# alarm_controller_f103.net
KiCad netlist of a schematic drawn in EAGLE
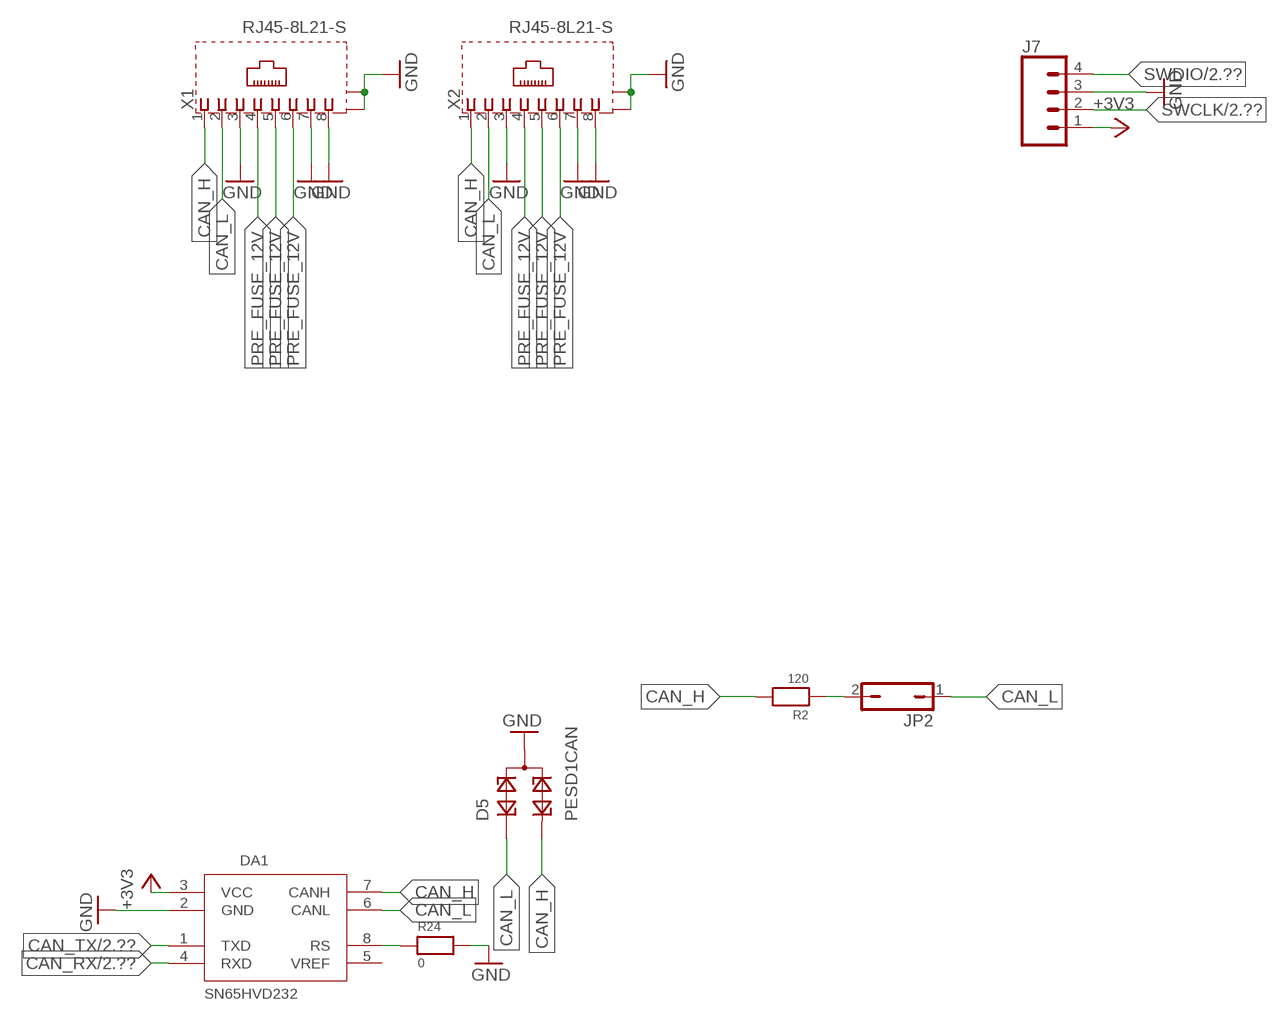
[diagram p0: schematic, sheet 1, part 1 of 2]
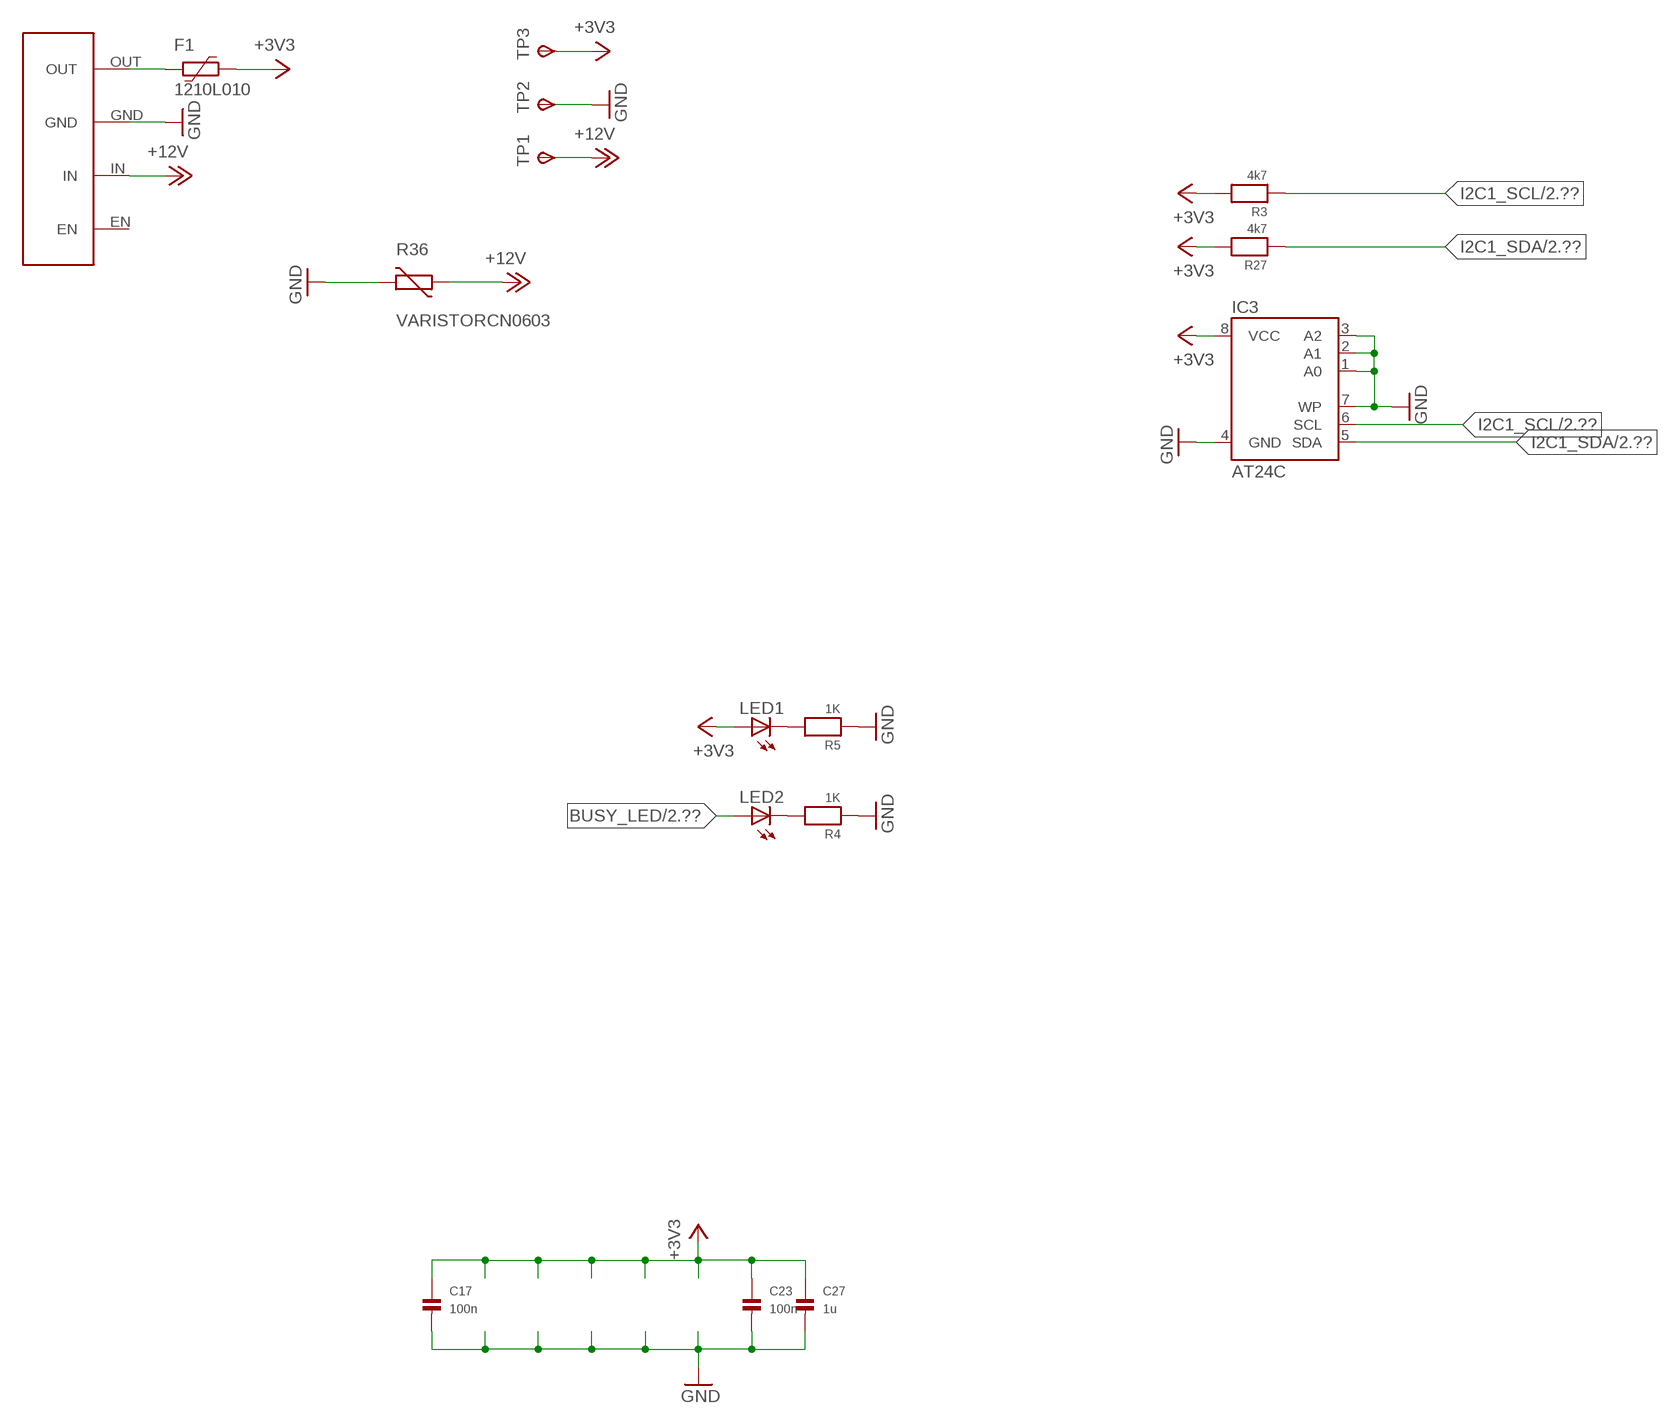
[diagram p1: schematic, sheet 1, part 2 of 2]
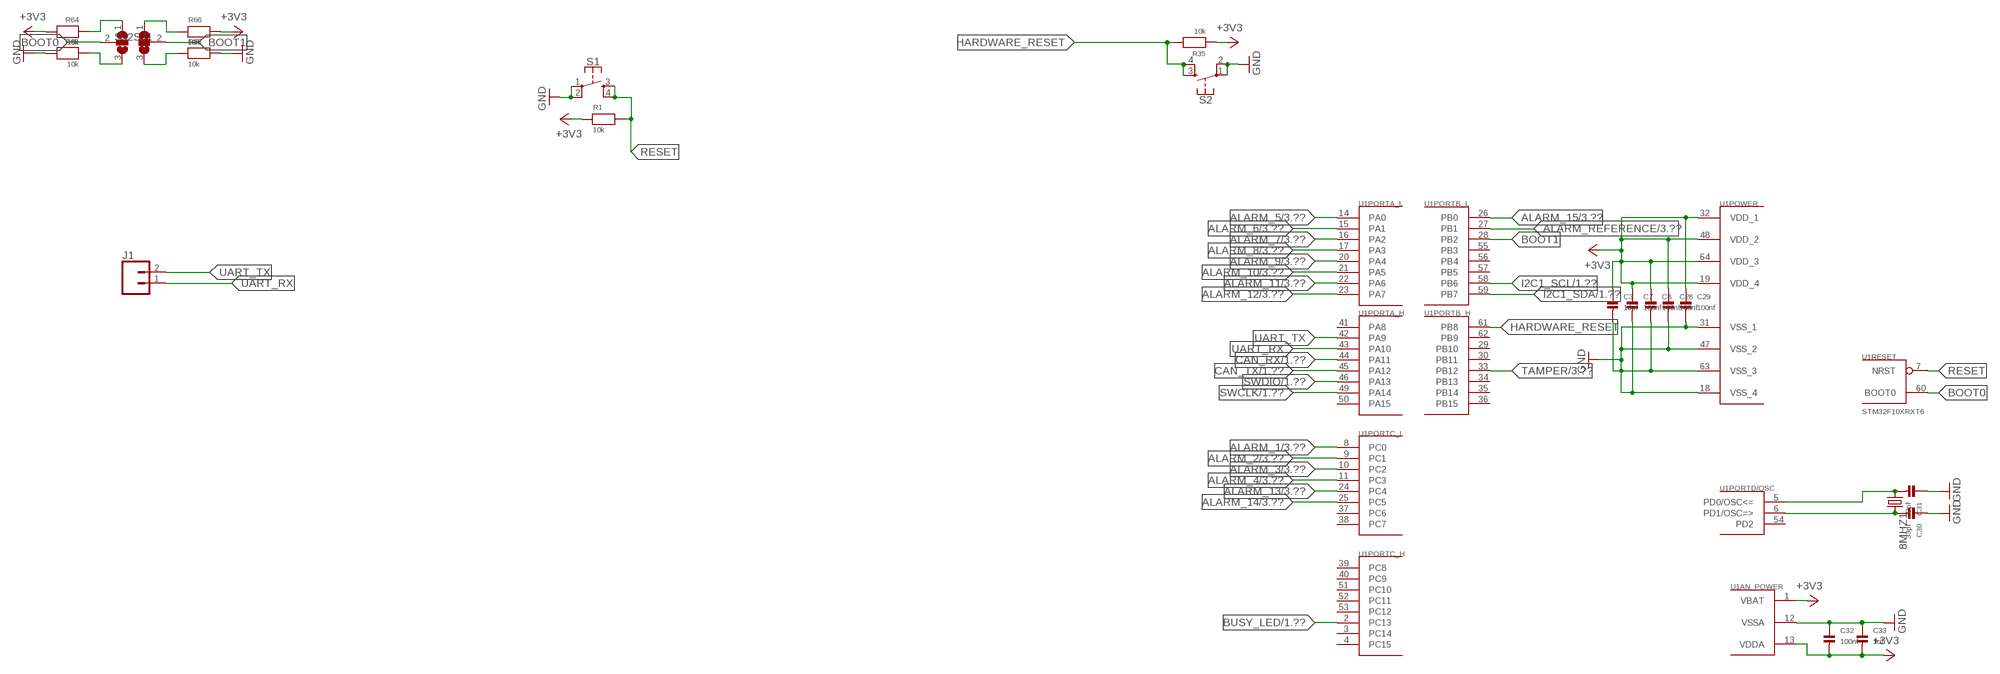
[diagram p2: schematic, sheet 2]
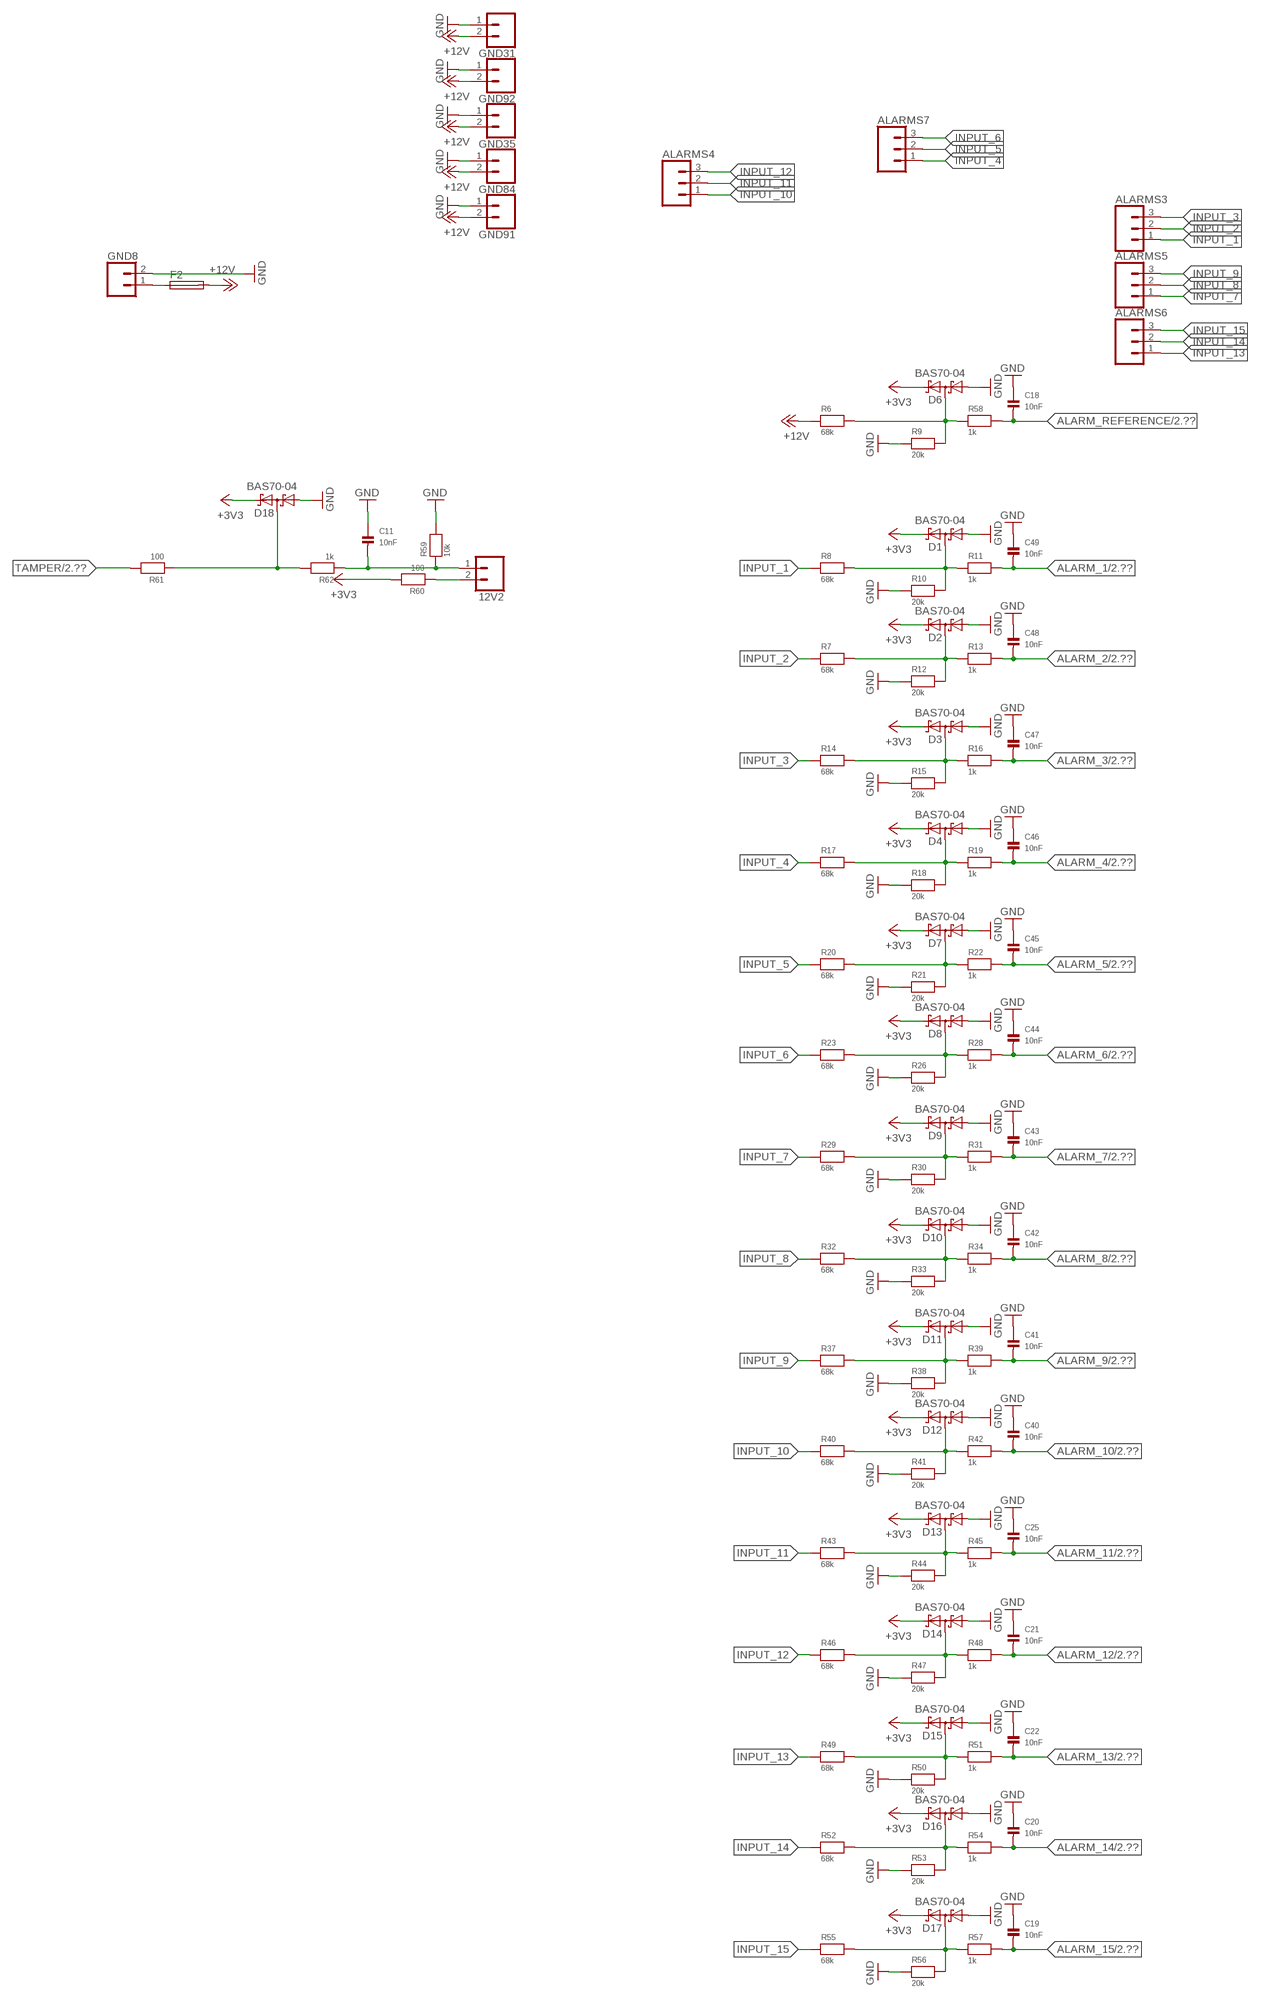
[diagram p3: schematic, sheet 3]

(export (version "E")
  (design (tool "Eeschema 10.0.6"))
  (components
    (comp (ref "C17")
      (value "100n")
      (footprint "eagle-import:0603")
      (libsource (lib "eagle-import") (part "CAP_CERAMIC0603"))
    )
    (comp (ref "C23")
      (value "100n")
      (footprint "eagle-import:0603")
      (libsource (lib "eagle-import") (part "CAP_CERAMIC0603"))
    )
    (comp (ref "C27")
      (value "1u")
      (footprint "eagle-import:0603")
      (libsource (lib "eagle-import") (part "CAP_CERAMIC0603"))
    )
    (comp (ref "D5")
      (value "PESD1CAN")
      (footprint "eagle-import:SOT23")
      (libsource (lib "eagle-import") (part "PESD1CAN"))
    )
    (comp (ref "DA1")
      (value "SN65HVD232")
      (footprint "eagle-import:SO08")
      (libsource (lib "eagle-import") (part "SN65HVD232"))
    )
    (comp (ref "F1")
      (value "1210L010")
      (footprint "eagle-import:1210L")
      (fields (field (name "MF") "Littelfuse"))
      (libsource (lib "eagle-import") (part "?1210L010"))
    )
    (comp (ref "IC3")
      (value "AT24C")
      (footprint "eagle-import:SOIC8")
      (libsource (lib "eagle-import") (part "AT24C"))
    )
    (comp (ref "J7")
      (value "CONN_04POLAR_LOCK")
      (footprint "eagle-import:MOLEX-1X4_LOCK")
      (libsource (lib "eagle-import") (part "CONN_04POLAR_LOCK"))
    )
    (comp (ref "JP2")
      (value "JP1Q")
      (footprint "eagle-import:JP1")
      (libsource (lib "eagle-import") (part "JP1Q"))
    )
    (comp (ref "LED1")
      (value "LEDCHIPLED_0805")
      (footprint "eagle-import:CHIPLED_0805")
      (libsource (lib "eagle-import") (part "LEDCHIPLED_0805"))
    )
    (comp (ref "LED2")
      (value "LEDCHIPLED_0805")
      (footprint "eagle-import:CHIPLED_0805")
      (libsource (lib "eagle-import") (part "LEDCHIPLED_0805"))
    )
    (comp (ref "R2")
      (value "120")
      (footprint "eagle-import:0603")
      (libsource (lib "eagle-import") (part "RESISTOR0603"))
    )
    (comp (ref "R3")
      (value "4k7")
      (footprint "eagle-import:0603")
      (libsource (lib "eagle-import") (part "RESISTOR0603"))
    )
    (comp (ref "R4")
      (value "1K")
      (footprint "eagle-import:0603")
      (libsource (lib "eagle-import") (part "RESISTOR0603"))
    )
    (comp (ref "R5")
      (value "1K")
      (footprint "eagle-import:0603")
      (libsource (lib "eagle-import") (part "RESISTOR0603"))
    )
    (comp (ref "R24")
      (value "0")
      (footprint "eagle-import:0603")
      (libsource (lib "eagle-import") (part "RESISTOR0603"))
    )
    (comp (ref "R27")
      (value "4k7")
      (footprint "eagle-import:0603")
      (libsource (lib "eagle-import") (part "RESISTOR0603"))
    )
    (comp (ref "R36")
      (value "VARISTORCN0603")
      (footprint "eagle-import:CT_CN0603")
      (libsource (lib "eagle-import") (part "VARISTORCN0603"))
    )
    (comp (ref "TP1")
      (value "TPSTP20R")
      (footprint "eagle-import:TP20R")
      (libsource (lib "eagle-import") (part "TPSTP20R"))
    )
    (comp (ref "TP2")
      (value "TPSTP20R")
      (footprint "eagle-import:TP20R")
      (libsource (lib "eagle-import") (part "TPSTP20R"))
    )
    (comp (ref "TP3")
      (value "TPSTP20R")
      (footprint "eagle-import:TP20R")
      (libsource (lib "eagle-import") (part "TPSTP20R"))
    )
    (comp (ref "U$4")
      (value "HW-613")
      (footprint "eagle-import:HW-613")
      (libsource (lib "eagle-import") (part "HW-613"))
    )
    (comp (ref "X1")
      (value "RJ45-8L21-S")
      (footprint "eagle-import:RJ45-SHIELD1")
      (libsource (lib "eagle-import") (part "RJ4521-S-8L"))
    )
    (comp (ref "X2")
      (value "RJ45-8L21-S")
      (footprint "eagle-import:RJ45-SHIELD1")
      (libsource (lib "eagle-import") (part "RJ4521-S-8L"))
    )
    (comp (ref "8MHZ1")
      (value "CRYSTALHC49UP")
      (footprint "eagle-import:HC49UP")
      (libsource (lib "eagle-import") (part "CRYSTALHC49UP"))
    )
    (comp (ref "C3")
      (value "10uf")
      (footprint "eagle-import:0805")
      (libsource (lib "eagle-import") (part "CAP_CERAMIC0805"))
    )
    (comp (ref "C7")
      (value "100nf")
      (footprint "eagle-import:0603-MINI")
      (libsource (lib "eagle-import") (part "CAP_CERAMIC0603MINI"))
    )
    (comp (ref "C8")
      (value "100nf")
      (footprint "eagle-import:0603-MINI")
      (libsource (lib "eagle-import") (part "CAP_CERAMIC0603MINI"))
    )
    (comp (ref "C28")
      (value "100nf")
      (footprint "eagle-import:0603-MINI")
      (libsource (lib "eagle-import") (part "CAP_CERAMIC0603MINI"))
    )
    (comp (ref "C29")
      (value "100nf")
      (footprint "eagle-import:0603-MINI")
      (libsource (lib "eagle-import") (part "CAP_CERAMIC0603MINI"))
    )
    (comp (ref "C30")
      (value "33pf")
      (footprint "eagle-import:0603")
      (libsource (lib "eagle-import") (part "CAP_CERAMIC0603"))
    )
    (comp (ref "C31")
      (value "33pf")
      (footprint "eagle-import:0603")
      (libsource (lib "eagle-import") (part "CAP_CERAMIC0603"))
    )
    (comp (ref "C32")
      (value "100nf")
      (footprint "eagle-import:0603-MINI")
      (libsource (lib "eagle-import") (part "CAP_CERAMIC0603MINI"))
    )
    (comp (ref "C33")
      (value "1uf")
      (footprint "eagle-import:0603-MINI")
      (libsource (lib "eagle-import") (part "CAP_CERAMIC0603MINI"))
    )
    (comp (ref "J1")
      (value "CONN_02")
      (footprint "eagle-import:1X02")
      (libsource (lib "eagle-import") (part "CONN_02"))
    )
    (comp (ref "R1")
      (value "10k")
      (footprint "eagle-import:0603")
      (libsource (lib "eagle-import") (part "RESISTOR0603"))
    )
    (comp (ref "R35")
      (value "10k")
      (footprint "eagle-import:0603")
      (libsource (lib "eagle-import") (part "RESISTOR0603"))
    )
    (comp (ref "R63")
      (value "10k")
      (footprint "eagle-import:0603")
      (libsource (lib "eagle-import") (part "RESISTOR0603"))
    )
    (comp (ref "R64")
      (value "10k")
      (footprint "eagle-import:0603")
      (libsource (lib "eagle-import") (part "RESISTOR0603"))
    )
    (comp (ref "R65")
      (value "10k")
      (footprint "eagle-import:0603")
      (libsource (lib "eagle-import") (part "RESISTOR0603"))
    )
    (comp (ref "R66")
      (value "10k")
      (footprint "eagle-import:0603")
      (libsource (lib "eagle-import") (part "RESISTOR0603"))
    )
    (comp (ref "S1")
      (value "MOMENTARY-SWITCH-SPST-2-SMD-4.6X2.8MM")
      (footprint "eagle-import:TACTILE_SWITCH_SMD_4.6X2.8MM")
      (libsource (lib "eagle-import") (part "MOMENTARY-SWITCH-SPST-2-SMD-4.6X2.8MM"))
    )
    (comp (ref "S2")
      (value "MOMENTARY-SWITCH-SPST-2-SMD-4.6X2.8MM")
      (footprint "eagle-import:TACTILE_SWITCH_SMD_4.6X2.8MM")
      (libsource (lib "eagle-import") (part "MOMENTARY-SWITCH-SPST-2-SMD-4.6X2.8MM"))
    )
    (comp (ref "SJ1")
      (value "SJ2W")
      (footprint "eagle-import:SJ_2")
      (libsource (lib "eagle-import") (part "SJ2W"))
    )
    (comp (ref "SJ2")
      (value "SJ2W")
      (footprint "eagle-import:SJ_2")
      (libsource (lib "eagle-import") (part "SJ2W"))
    )
    (comp (ref "U1")
      (value "STM32F10XRXT6")
      (footprint "eagle-import:TQFP64")
      (libsource (lib "eagle-import") (part "STM32F10XRXT6"))
    )
    (comp (ref "12V2")
      (value "CONN_023.5MM")
      (footprint "eagle-import:SCREWTERMINAL-3.5MM-2")
      (libsource (lib "eagle-import") (part "CONN_023.5MM"))
    )
    (comp (ref "ALARMS3")
      (value "CONN_03SCREW_LOCK")
      (footprint "eagle-import:SCREWTERMINAL-3.5MM-3_LOCK.007S")
      (libsource (lib "eagle-import") (part "CONN_03SCREW_LOCK"))
    )
    (comp (ref "ALARMS4")
      (value "CONN_03SCREW_LOCK")
      (footprint "eagle-import:SCREWTERMINAL-3.5MM-3_LOCK.007S")
      (libsource (lib "eagle-import") (part "CONN_03SCREW_LOCK"))
    )
    (comp (ref "ALARMS5")
      (value "CONN_03SCREW_LOCK")
      (footprint "eagle-import:SCREWTERMINAL-3.5MM-3_LOCK.007S")
      (libsource (lib "eagle-import") (part "CONN_03SCREW_LOCK"))
    )
    (comp (ref "ALARMS6")
      (value "CONN_03SCREW_LOCK")
      (footprint "eagle-import:SCREWTERMINAL-3.5MM-3_LOCK.007S")
      (libsource (lib "eagle-import") (part "CONN_03SCREW_LOCK"))
    )
    (comp (ref "ALARMS7")
      (value "CONN_03SCREW_LOCK")
      (footprint "eagle-import:SCREWTERMINAL-3.5MM-3_LOCK.007S")
      (libsource (lib "eagle-import") (part "CONN_03SCREW_LOCK"))
    )
    (comp (ref "C11")
      (value "10nF")
      (footprint "eagle-import:0603")
      (libsource (lib "eagle-import") (part "CAP_CERAMIC0603"))
    )
    (comp (ref "C18")
      (value "10nF")
      (footprint "eagle-import:0603")
      (libsource (lib "eagle-import") (part "CAP_CERAMIC0603"))
    )
    (comp (ref "C19")
      (value "10nF")
      (footprint "eagle-import:0603")
      (libsource (lib "eagle-import") (part "CAP_CERAMIC0603"))
    )
    (comp (ref "C20")
      (value "10nF")
      (footprint "eagle-import:0603")
      (libsource (lib "eagle-import") (part "CAP_CERAMIC0603"))
    )
    (comp (ref "C21")
      (value "10nF")
      (footprint "eagle-import:0603")
      (libsource (lib "eagle-import") (part "CAP_CERAMIC0603"))
    )
    (comp (ref "C22")
      (value "10nF")
      (footprint "eagle-import:0603")
      (libsource (lib "eagle-import") (part "CAP_CERAMIC0603"))
    )
    (comp (ref "C25")
      (value "10nF")
      (footprint "eagle-import:0603")
      (libsource (lib "eagle-import") (part "CAP_CERAMIC0603"))
    )
    (comp (ref "C40")
      (value "10nF")
      (footprint "eagle-import:0603")
      (libsource (lib "eagle-import") (part "CAP_CERAMIC0603"))
    )
    (comp (ref "C41")
      (value "10nF")
      (footprint "eagle-import:0603")
      (libsource (lib "eagle-import") (part "CAP_CERAMIC0603"))
    )
    (comp (ref "C42")
      (value "10nF")
      (footprint "eagle-import:0603")
      (libsource (lib "eagle-import") (part "CAP_CERAMIC0603"))
    )
    (comp (ref "C43")
      (value "10nF")
      (footprint "eagle-import:0603")
      (libsource (lib "eagle-import") (part "CAP_CERAMIC0603"))
    )
    (comp (ref "C44")
      (value "10nF")
      (footprint "eagle-import:0603")
      (libsource (lib "eagle-import") (part "CAP_CERAMIC0603"))
    )
    (comp (ref "C45")
      (value "10nF")
      (footprint "eagle-import:0603")
      (libsource (lib "eagle-import") (part "CAP_CERAMIC0603"))
    )
    (comp (ref "C46")
      (value "10nF")
      (footprint "eagle-import:0603")
      (libsource (lib "eagle-import") (part "CAP_CERAMIC0603"))
    )
    (comp (ref "C47")
      (value "10nF")
      (footprint "eagle-import:0603")
      (libsource (lib "eagle-import") (part "CAP_CERAMIC0603"))
    )
    (comp (ref "C48")
      (value "10nF")
      (footprint "eagle-import:0603")
      (libsource (lib "eagle-import") (part "CAP_CERAMIC0603"))
    )
    (comp (ref "C49")
      (value "10nF")
      (footprint "eagle-import:0603")
      (libsource (lib "eagle-import") (part "CAP_CERAMIC0603"))
    )
    (comp (ref "D1")
      (value "BAS70-04")
      (footprint "eagle-import:SOT23")
      (libsource (lib "eagle-import") (part "BAS70-04"))
    )
    (comp (ref "D2")
      (value "BAS70-04")
      (footprint "eagle-import:SOT23")
      (libsource (lib "eagle-import") (part "BAS70-04"))
    )
    (comp (ref "D3")
      (value "BAS70-04")
      (footprint "eagle-import:SOT23")
      (libsource (lib "eagle-import") (part "BAS70-04"))
    )
    (comp (ref "D4")
      (value "BAS70-04")
      (footprint "eagle-import:SOT23")
      (libsource (lib "eagle-import") (part "BAS70-04"))
    )
    (comp (ref "D6")
      (value "BAS70-04")
      (footprint "eagle-import:SOT23")
      (libsource (lib "eagle-import") (part "BAS70-04"))
    )
    (comp (ref "D7")
      (value "BAS70-04")
      (footprint "eagle-import:SOT23")
      (libsource (lib "eagle-import") (part "BAS70-04"))
    )
    (comp (ref "D8")
      (value "BAS70-04")
      (footprint "eagle-import:SOT23")
      (libsource (lib "eagle-import") (part "BAS70-04"))
    )
    (comp (ref "D9")
      (value "BAS70-04")
      (footprint "eagle-import:SOT23")
      (libsource (lib "eagle-import") (part "BAS70-04"))
    )
    (comp (ref "D10")
      (value "BAS70-04")
      (footprint "eagle-import:SOT23")
      (libsource (lib "eagle-import") (part "BAS70-04"))
    )
    (comp (ref "D11")
      (value "BAS70-04")
      (footprint "eagle-import:SOT23")
      (libsource (lib "eagle-import") (part "BAS70-04"))
    )
    (comp (ref "D12")
      (value "BAS70-04")
      (footprint "eagle-import:SOT23")
      (libsource (lib "eagle-import") (part "BAS70-04"))
    )
    (comp (ref "D13")
      (value "BAS70-04")
      (footprint "eagle-import:SOT23")
      (libsource (lib "eagle-import") (part "BAS70-04"))
    )
    (comp (ref "D14")
      (value "BAS70-04")
      (footprint "eagle-import:SOT23")
      (libsource (lib "eagle-import") (part "BAS70-04"))
    )
    (comp (ref "D15")
      (value "BAS70-04")
      (footprint "eagle-import:SOT23")
      (libsource (lib "eagle-import") (part "BAS70-04"))
    )
    (comp (ref "D16")
      (value "BAS70-04")
      (footprint "eagle-import:SOT23")
      (libsource (lib "eagle-import") (part "BAS70-04"))
    )
    (comp (ref "D17")
      (value "BAS70-04")
      (footprint "eagle-import:SOT23")
      (libsource (lib "eagle-import") (part "BAS70-04"))
    )
    (comp (ref "D18")
      (value "BAS70-04")
      (footprint "eagle-import:SOT23")
      (libsource (lib "eagle-import") (part "BAS70-04"))
    )
    (comp (ref "F2")
      (value "TE5")
      (footprint "eagle-import:TE5")
      (libsource (lib "eagle-import") (part "TE5"))
    )
    (comp (ref "GND8")
      (value "CONN_025MM")
      (footprint "eagle-import:SCREWTERMINAL-5MM-2")
      (libsource (lib "eagle-import") (part "CONN_025MM"))
    )
    (comp (ref "GND31")
      (value "CONN_023.5MM")
      (footprint "eagle-import:SCREWTERMINAL-3.5MM-2")
      (libsource (lib "eagle-import") (part "CONN_023.5MM"))
    )
    (comp (ref "GND35")
      (value "CONN_023.5MM")
      (footprint "eagle-import:SCREWTERMINAL-3.5MM-2")
      (libsource (lib "eagle-import") (part "CONN_023.5MM"))
    )
    (comp (ref "GND84")
      (value "CONN_023.5MM")
      (footprint "eagle-import:SCREWTERMINAL-3.5MM-2")
      (libsource (lib "eagle-import") (part "CONN_023.5MM"))
    )
    (comp (ref "GND91")
      (value "CONN_023.5MM")
      (footprint "eagle-import:SCREWTERMINAL-3.5MM-2")
      (libsource (lib "eagle-import") (part "CONN_023.5MM"))
    )
    (comp (ref "GND92")
      (value "CONN_023.5MM")
      (footprint "eagle-import:SCREWTERMINAL-3.5MM-2")
      (libsource (lib "eagle-import") (part "CONN_023.5MM"))
    )
    (comp (ref "R6")
      (value "68k")
      (footprint "eagle-import:0603")
      (libsource (lib "eagle-import") (part "RESISTOR0603"))
    )
    (comp (ref "R7")
      (value "68k")
      (footprint "eagle-import:0603")
      (libsource (lib "eagle-import") (part "RESISTOR0603"))
    )
    (comp (ref "R8")
      (value "68k")
      (footprint "eagle-import:0603")
      (libsource (lib "eagle-import") (part "RESISTOR0603"))
    )
    (comp (ref "R9")
      (value "20k")
      (footprint "eagle-import:0603")
      (libsource (lib "eagle-import") (part "RESISTOR0603"))
    )
    (comp (ref "R10")
      (value "20k")
      (footprint "eagle-import:0603")
      (libsource (lib "eagle-import") (part "RESISTOR0603"))
    )
    (comp (ref "R11")
      (value "1k")
      (footprint "eagle-import:0603")
      (libsource (lib "eagle-import") (part "RESISTOR0603"))
    )
    (comp (ref "R12")
      (value "20k")
      (footprint "eagle-import:0603")
      (libsource (lib "eagle-import") (part "RESISTOR0603"))
    )
    (comp (ref "R13")
      (value "1k")
      (footprint "eagle-import:0603")
      (libsource (lib "eagle-import") (part "RESISTOR0603"))
    )
    (comp (ref "R14")
      (value "68k")
      (footprint "eagle-import:0603")
      (libsource (lib "eagle-import") (part "RESISTOR0603"))
    )
    (comp (ref "R15")
      (value "20k")
      (footprint "eagle-import:0603")
      (libsource (lib "eagle-import") (part "RESISTOR0603"))
    )
    (comp (ref "R16")
      (value "1k")
      (footprint "eagle-import:0603")
      (libsource (lib "eagle-import") (part "RESISTOR0603"))
    )
    (comp (ref "R17")
      (value "68k")
      (footprint "eagle-import:0603")
      (libsource (lib "eagle-import") (part "RESISTOR0603"))
    )
    (comp (ref "R18")
      (value "20k")
      (footprint "eagle-import:0603")
      (libsource (lib "eagle-import") (part "RESISTOR0603"))
    )
    (comp (ref "R19")
      (value "1k")
      (footprint "eagle-import:0603")
      (libsource (lib "eagle-import") (part "RESISTOR0603"))
    )
    (comp (ref "R20")
      (value "68k")
      (footprint "eagle-import:0603")
      (libsource (lib "eagle-import") (part "RESISTOR0603"))
    )
    (comp (ref "R21")
      (value "20k")
      (footprint "eagle-import:0603")
      (libsource (lib "eagle-import") (part "RESISTOR0603"))
    )
    (comp (ref "R22")
      (value "1k")
      (footprint "eagle-import:0603")
      (libsource (lib "eagle-import") (part "RESISTOR0603"))
    )
    (comp (ref "R23")
      (value "68k")
      (footprint "eagle-import:0603")
      (libsource (lib "eagle-import") (part "RESISTOR0603"))
    )
    (comp (ref "R26")
      (value "20k")
      (footprint "eagle-import:0603")
      (libsource (lib "eagle-import") (part "RESISTOR0603"))
    )
    (comp (ref "R28")
      (value "1k")
      (footprint "eagle-import:0603")
      (libsource (lib "eagle-import") (part "RESISTOR0603"))
    )
    (comp (ref "R29")
      (value "68k")
      (footprint "eagle-import:0603")
      (libsource (lib "eagle-import") (part "RESISTOR0603"))
    )
    (comp (ref "R30")
      (value "20k")
      (footprint "eagle-import:0603")
      (libsource (lib "eagle-import") (part "RESISTOR0603"))
    )
    (comp (ref "R31")
      (value "1k")
      (footprint "eagle-import:0603")
      (libsource (lib "eagle-import") (part "RESISTOR0603"))
    )
    (comp (ref "R32")
      (value "68k")
      (footprint "eagle-import:0603")
      (libsource (lib "eagle-import") (part "RESISTOR0603"))
    )
    (comp (ref "R33")
      (value "20k")
      (footprint "eagle-import:0603")
      (libsource (lib "eagle-import") (part "RESISTOR0603"))
    )
    (comp (ref "R34")
      (value "1k")
      (footprint "eagle-import:0603")
      (libsource (lib "eagle-import") (part "RESISTOR0603"))
    )
    (comp (ref "R37")
      (value "68k")
      (footprint "eagle-import:0603")
      (libsource (lib "eagle-import") (part "RESISTOR0603"))
    )
    (comp (ref "R38")
      (value "20k")
      (footprint "eagle-import:0603")
      (libsource (lib "eagle-import") (part "RESISTOR0603"))
    )
    (comp (ref "R39")
      (value "1k")
      (footprint "eagle-import:0603")
      (libsource (lib "eagle-import") (part "RESISTOR0603"))
    )
    (comp (ref "R40")
      (value "68k")
      (footprint "eagle-import:0603")
      (libsource (lib "eagle-import") (part "RESISTOR0603"))
    )
    (comp (ref "R41")
      (value "20k")
      (footprint "eagle-import:0603")
      (libsource (lib "eagle-import") (part "RESISTOR0603"))
    )
    (comp (ref "R42")
      (value "1k")
      (footprint "eagle-import:0603")
      (libsource (lib "eagle-import") (part "RESISTOR0603"))
    )
    (comp (ref "R43")
      (value "68k")
      (footprint "eagle-import:0603")
      (libsource (lib "eagle-import") (part "RESISTOR0603"))
    )
    (comp (ref "R44")
      (value "20k")
      (footprint "eagle-import:0603")
      (libsource (lib "eagle-import") (part "RESISTOR0603"))
    )
    (comp (ref "R45")
      (value "1k")
      (footprint "eagle-import:0603")
      (libsource (lib "eagle-import") (part "RESISTOR0603"))
    )
    (comp (ref "R46")
      (value "68k")
      (footprint "eagle-import:0603")
      (libsource (lib "eagle-import") (part "RESISTOR0603"))
    )
    (comp (ref "R47")
      (value "20k")
      (footprint "eagle-import:0603")
      (libsource (lib "eagle-import") (part "RESISTOR0603"))
    )
    (comp (ref "R48")
      (value "1k")
      (footprint "eagle-import:0603")
      (libsource (lib "eagle-import") (part "RESISTOR0603"))
    )
    (comp (ref "R49")
      (value "68k")
      (footprint "eagle-import:0603")
      (libsource (lib "eagle-import") (part "RESISTOR0603"))
    )
    (comp (ref "R50")
      (value "20k")
      (footprint "eagle-import:0603")
      (libsource (lib "eagle-import") (part "RESISTOR0603"))
    )
    (comp (ref "R51")
      (value "1k")
      (footprint "eagle-import:0603")
      (libsource (lib "eagle-import") (part "RESISTOR0603"))
    )
    (comp (ref "R52")
      (value "68k")
      (footprint "eagle-import:0603")
      (libsource (lib "eagle-import") (part "RESISTOR0603"))
    )
    (comp (ref "R53")
      (value "20k")
      (footprint "eagle-import:0603")
      (libsource (lib "eagle-import") (part "RESISTOR0603"))
    )
    (comp (ref "R54")
      (value "1k")
      (footprint "eagle-import:0603")
      (libsource (lib "eagle-import") (part "RESISTOR0603"))
    )
    (comp (ref "R55")
      (value "68k")
      (footprint "eagle-import:0603")
      (libsource (lib "eagle-import") (part "RESISTOR0603"))
    )
    (comp (ref "R56")
      (value "20k")
      (footprint "eagle-import:0603")
      (libsource (lib "eagle-import") (part "RESISTOR0603"))
    )
    (comp (ref "R57")
      (value "1k")
      (footprint "eagle-import:0603")
      (libsource (lib "eagle-import") (part "RESISTOR0603"))
    )
    (comp (ref "R58")
      (value "1k")
      (footprint "eagle-import:0603")
      (libsource (lib "eagle-import") (part "RESISTOR0603"))
    )
    (comp (ref "R59")
      (value "10k")
      (footprint "eagle-import:0603")
      (libsource (lib "eagle-import") (part "RESISTOR0603"))
    )
    (comp (ref "R60")
      (value "100")
      (footprint "eagle-import:0603")
      (libsource (lib "eagle-import") (part "RESISTOR0603"))
    )
    (comp (ref "R61")
      (value "100")
      (footprint "eagle-import:0603")
      (libsource (lib "eagle-import") (part "RESISTOR0603"))
    )
    (comp (ref "R62")
      (value "1k")
      (footprint "eagle-import:0603")
      (libsource (lib "eagle-import") (part "RESISTOR0603"))
    )
  )
  (nets
    (net (code "1") (name "+3V3") (class "Default")
      (node (ref "C17") (pin "1") (pinfunction "P$1_1") (pintype "passive"))
      (node (ref "C23") (pin "1") (pinfunction "P$1_1") (pintype "passive"))
      (node (ref "C27") (pin "1") (pinfunction "P$1_1") (pintype "passive"))
      (node (ref "C28") (pin "1") (pinfunction "P$1_1") (pintype "passive"))
      (node (ref "C29") (pin "1") (pinfunction "P$1_1") (pintype "passive"))
      (node (ref "C3") (pin "1") (pinfunction "P$1_1") (pintype "passive"))
      (node (ref "C32") (pin "2") (pinfunction "P$2_2") (pintype "passive"))
      (node (ref "C33") (pin "2") (pinfunction "P$2_2") (pintype "passive"))
      (node (ref "C7") (pin "1") (pinfunction "P$1_1") (pintype "passive"))
      (node (ref "C8") (pin "1") (pinfunction "P$1_1") (pintype "passive"))
      (node (ref "D1") (pin "2") (pinfunction "C2_2") (pintype "passive"))
      (node (ref "D10") (pin "2") (pinfunction "C2_2") (pintype "passive"))
      (node (ref "D11") (pin "2") (pinfunction "C2_2") (pintype "passive"))
      (node (ref "D12") (pin "2") (pinfunction "C2_2") (pintype "passive"))
      (node (ref "D13") (pin "2") (pinfunction "C2_2") (pintype "passive"))
      (node (ref "D14") (pin "2") (pinfunction "C2_2") (pintype "passive"))
      (node (ref "D15") (pin "2") (pinfunction "C2_2") (pintype "passive"))
      (node (ref "D16") (pin "2") (pinfunction "C2_2") (pintype "passive"))
      (node (ref "D17") (pin "2") (pinfunction "C2_2") (pintype "passive"))
      (node (ref "D18") (pin "2") (pinfunction "C2_2") (pintype "passive"))
      (node (ref "D2") (pin "2") (pinfunction "C2_2") (pintype "passive"))
      (node (ref "D3") (pin "2") (pinfunction "C2_2") (pintype "passive"))
      (node (ref "D4") (pin "2") (pinfunction "C2_2") (pintype "passive"))
      (node (ref "D6") (pin "2") (pinfunction "C2_2") (pintype "passive"))
      (node (ref "D7") (pin "2") (pinfunction "C2_2") (pintype "passive"))
      (node (ref "D8") (pin "2") (pinfunction "C2_2") (pintype "passive"))
      (node (ref "D9") (pin "2") (pinfunction "C2_2") (pintype "passive"))
      (node (ref "DA1") (pin "3") (pinfunction "VCC_3") (pintype "power_in"))
      (node (ref "F1") (pin "1") (pinfunction "1_1") (pintype "passive"))
      (node (ref "IC3") (pin "8") (pinfunction "VCC_8") (pintype "power_in"))
      (node (ref "J7") (pin "1") (pinfunction "1_1") (pintype "passive"))
      (node (ref "LED1") (pin "A") (pinfunction "A_A") (pintype "passive"))
      (node (ref "R1") (pin "1") (pinfunction "1_1") (pintype "passive"))
      (node (ref "R27") (pin "2") (pinfunction "2_2") (pintype "passive"))
      (node (ref "R3") (pin "2") (pinfunction "2_2") (pintype "passive"))
      (node (ref "R35") (pin "1") (pinfunction "1_1") (pintype "passive"))
      (node (ref "R60") (pin "2") (pinfunction "2_2") (pintype "passive"))
      (node (ref "R64") (pin "2") (pinfunction "2_2") (pintype "passive"))
      (node (ref "R66") (pin "2") (pinfunction "2_2") (pintype "passive"))
      (node (ref "TP3") (pin "TP") (pinfunction "PP_TP") (pintype "input"))
      (node (ref "U1") (pin "1") (pinfunction "VBAT_1") (pintype "power_in"))
      (node (ref "U1") (pin "13") (pinfunction "VDDA_13") (pintype "power_in"))
      (node (ref "U1") (pin "19") (pinfunction "VDD_4_19") (pintype "power_in"))
      (node (ref "U1") (pin "32") (pinfunction "VDD_1_32") (pintype "power_in"))
      (node (ref "U1") (pin "48") (pinfunction "VDD_2_48") (pintype "power_in"))
      (node (ref "U1") (pin "64") (pinfunction "VDD_3_64") (pintype "power_in"))
    )
    (net (code "2") (name "+12V") (class "Default")
      (node (ref "F2") (pin "2") (pinfunction "2_2") (pintype "passive"))
      (node (ref "GND31") (pin "2") (pinfunction "2_2") (pintype "passive"))
      (node (ref "GND35") (pin "2") (pinfunction "2_2") (pintype "passive"))
      (node (ref "GND84") (pin "2") (pinfunction "2_2") (pintype "passive"))
      (node (ref "GND91") (pin "2") (pinfunction "2_2") (pintype "passive"))
      (node (ref "GND92") (pin "2") (pinfunction "2_2") (pintype "passive"))
      (node (ref "R36") (pin "1") (pinfunction "1_1") (pintype "passive"))
      (node (ref "R6") (pin "1") (pinfunction "1_1") (pintype "passive"))
      (node (ref "TP1") (pin "TP") (pinfunction "PP_TP") (pintype "input"))
      (node (ref "U$4") (pin "IN") (pinfunction "IN_IN") (pintype "bidirectional"))
    )
    (net (code "3") (name "ALARM_1") (class "Default")
      (node (ref "C49") (pin "2") (pinfunction "P$2_2") (pintype "passive"))
      (node (ref "R11") (pin "2") (pinfunction "2_2") (pintype "passive"))
      (node (ref "U1") (pin "8") (pinfunction "PC0_8") (pintype "bidirectional"))
    )
    (net (code "4") (name "ALARM_2") (class "Default")
      (node (ref "C48") (pin "2") (pinfunction "P$2_2") (pintype "passive"))
      (node (ref "R13") (pin "2") (pinfunction "2_2") (pintype "passive"))
      (node (ref "U1") (pin "9") (pinfunction "PC1_9") (pintype "bidirectional"))
    )
    (net (code "5") (name "ALARM_3") (class "Default")
      (node (ref "C47") (pin "2") (pinfunction "P$2_2") (pintype "passive"))
      (node (ref "R16") (pin "2") (pinfunction "2_2") (pintype "passive"))
      (node (ref "U1") (pin "10") (pinfunction "PC2_10") (pintype "bidirectional"))
    )
    (net (code "6") (name "ALARM_4") (class "Default")
      (node (ref "C46") (pin "2") (pinfunction "P$2_2") (pintype "passive"))
      (node (ref "R19") (pin "2") (pinfunction "2_2") (pintype "passive"))
      (node (ref "U1") (pin "11") (pinfunction "PC3_11") (pintype "bidirectional"))
    )
    (net (code "7") (name "ALARM_5") (class "Default")
      (node (ref "C45") (pin "2") (pinfunction "P$2_2") (pintype "passive"))
      (node (ref "R22") (pin "2") (pinfunction "2_2") (pintype "passive"))
      (node (ref "U1") (pin "14") (pinfunction "PA0_14") (pintype "bidirectional"))
    )
    (net (code "8") (name "ALARM_6") (class "Default")
      (node (ref "C44") (pin "2") (pinfunction "P$2_2") (pintype "passive"))
      (node (ref "R28") (pin "2") (pinfunction "2_2") (pintype "passive"))
      (node (ref "U1") (pin "15") (pinfunction "PA1_15") (pintype "bidirectional"))
    )
    (net (code "9") (name "ALARM_7") (class "Default")
      (node (ref "C43") (pin "2") (pinfunction "P$2_2") (pintype "passive"))
      (node (ref "R31") (pin "2") (pinfunction "2_2") (pintype "passive"))
      (node (ref "U1") (pin "16") (pinfunction "PA2_16") (pintype "bidirectional"))
    )
    (net (code "10") (name "ALARM_8") (class "Default")
      (node (ref "C42") (pin "2") (pinfunction "P$2_2") (pintype "passive"))
      (node (ref "R34") (pin "2") (pinfunction "2_2") (pintype "passive"))
      (node (ref "U1") (pin "17") (pinfunction "PA3_17") (pintype "bidirectional"))
    )
    (net (code "11") (name "ALARM_9") (class "Default")
      (node (ref "C41") (pin "2") (pinfunction "P$2_2") (pintype "passive"))
      (node (ref "R39") (pin "2") (pinfunction "2_2") (pintype "passive"))
      (node (ref "U1") (pin "20") (pinfunction "PA4_20") (pintype "bidirectional"))
    )
    (net (code "12") (name "ALARM_10") (class "Default")
      (node (ref "C40") (pin "2") (pinfunction "P$2_2") (pintype "passive"))
      (node (ref "R42") (pin "2") (pinfunction "2_2") (pintype "passive"))
      (node (ref "U1") (pin "21") (pinfunction "PA5_21") (pintype "bidirectional"))
    )
    (net (code "13") (name "ALARM_11") (class "Default")
      (node (ref "C25") (pin "2") (pinfunction "P$2_2") (pintype "passive"))
      (node (ref "R45") (pin "2") (pinfunction "2_2") (pintype "passive"))
      (node (ref "U1") (pin "22") (pinfunction "PA6_22") (pintype "bidirectional"))
    )
    (net (code "14") (name "ALARM_12") (class "Default")
      (node (ref "C21") (pin "2") (pinfunction "P$2_2") (pintype "passive"))
      (node (ref "R48") (pin "2") (pinfunction "2_2") (pintype "passive"))
      (node (ref "U1") (pin "23") (pinfunction "PA7_23") (pintype "bidirectional"))
    )
    (net (code "15") (name "ALARM_13") (class "Default")
      (node (ref "C22") (pin "2") (pinfunction "P$2_2") (pintype "passive"))
      (node (ref "R51") (pin "2") (pinfunction "2_2") (pintype "passive"))
      (node (ref "U1") (pin "24") (pinfunction "PC4_24") (pintype "bidirectional"))
    )
    (net (code "16") (name "ALARM_14") (class "Default")
      (node (ref "C20") (pin "2") (pinfunction "P$2_2") (pintype "passive"))
      (node (ref "R54") (pin "2") (pinfunction "2_2") (pintype "passive"))
      (node (ref "U1") (pin "25") (pinfunction "PC5_25") (pintype "bidirectional"))
    )
    (net (code "17") (name "ALARM_15") (class "Default")
      (node (ref "C19") (pin "2") (pinfunction "P$2_2") (pintype "passive"))
      (node (ref "R57") (pin "2") (pinfunction "2_2") (pintype "passive"))
      (node (ref "U1") (pin "26") (pinfunction "PB0_26") (pintype "bidirectional"))
    )
    (net (code "18") (name "ALARM_REFERENCE") (class "Default")
      (node (ref "C18") (pin "2") (pinfunction "P$2_2") (pintype "passive"))
      (node (ref "R58") (pin "2") (pinfunction "2_2") (pintype "passive"))
      (node (ref "U1") (pin "27") (pinfunction "PB1_27") (pintype "bidirectional"))
    )
    (net (code "19") (name "BOOT0") (class "Default")
      (node (ref "SJ1") (pin "2") (pinfunction "2_2") (pintype "passive"))
      (node (ref "U1") (pin "60") (pinfunction "BOOT0_60") (pintype "input"))
    )
    (net (code "20") (name "BOOT1") (class "Default")
      (node (ref "SJ2") (pin "2") (pinfunction "2_2") (pintype "passive"))
      (node (ref "U1") (pin "28") (pinfunction "PB2_28") (pintype "bidirectional"))
    )
    (net (code "21") (name "BUSY_LED") (class "Default")
      (node (ref "LED2") (pin "A") (pinfunction "A_A") (pintype "passive"))
      (node (ref "U1") (pin "2") (pinfunction "PC13_2") (pintype "bidirectional"))
    )
    (net (code "22") (name "CAN_H") (class "Default")
      (node (ref "D5") (pin "2") (pinfunction "2_2") (pintype "passive"))
      (node (ref "DA1") (pin "7") (pinfunction "CANH_7") (pintype "bidirectional"))
      (node (ref "R2") (pin "2") (pinfunction "2_2") (pintype "passive"))
      (node (ref "X1") (pin "1") (pinfunction "1_1") (pintype "passive"))
      (node (ref "X2") (pin "1") (pinfunction "1_1") (pintype "passive"))
    )
    (net (code "23") (name "CAN_L") (class "Default")
      (node (ref "D5") (pin "1") (pinfunction "1_1") (pintype "passive"))
      (node (ref "DA1") (pin "6") (pinfunction "CANL_6") (pintype "bidirectional"))
      (node (ref "JP2") (pin "1") (pinfunction "1_1") (pintype "passive"))
      (node (ref "X1") (pin "2") (pinfunction "2_2") (pintype "passive"))
      (node (ref "X2") (pin "2") (pinfunction "2_2") (pintype "passive"))
    )
    (net (code "24") (name "CAN_RX") (class "Default")
      (node (ref "DA1") (pin "4") (pinfunction "RXD_4") (pintype "output"))
      (node (ref "U1") (pin "44") (pinfunction "PA11_44") (pintype "bidirectional"))
    )
    (net (code "25") (name "CAN_TX") (class "Default")
      (node (ref "DA1") (pin "1") (pinfunction "TXD_1") (pintype "input"))
      (node (ref "U1") (pin "45") (pinfunction "PA12_45") (pintype "bidirectional"))
    )
    (net (code "26") (name "GND") (class "Default")
      (node (ref "C11") (pin "1") (pinfunction "P$1_1") (pintype "passive"))
      (node (ref "C17") (pin "2") (pinfunction "P$2_2") (pintype "passive"))
      (node (ref "C18") (pin "1") (pinfunction "P$1_1") (pintype "passive"))
      (node (ref "C19") (pin "1") (pinfunction "P$1_1") (pintype "passive"))
      (node (ref "C20") (pin "1") (pinfunction "P$1_1") (pintype "passive"))
      (node (ref "C21") (pin "1") (pinfunction "P$1_1") (pintype "passive"))
      (node (ref "C22") (pin "1") (pinfunction "P$1_1") (pintype "passive"))
      (node (ref "C23") (pin "2") (pinfunction "P$2_2") (pintype "passive"))
      (node (ref "C25") (pin "1") (pinfunction "P$1_1") (pintype "passive"))
      (node (ref "C27") (pin "2") (pinfunction "P$2_2") (pintype "passive"))
      (node (ref "C28") (pin "2") (pinfunction "P$2_2") (pintype "passive"))
      (node (ref "C29") (pin "2") (pinfunction "P$2_2") (pintype "passive"))
      (node (ref "C3") (pin "2") (pinfunction "P$2_2") (pintype "passive"))
      (node (ref "C30") (pin "1") (pinfunction "P$1_1") (pintype "passive"))
      (node (ref "C31") (pin "1") (pinfunction "P$1_1") (pintype "passive"))
      (node (ref "C32") (pin "1") (pinfunction "P$1_1") (pintype "passive"))
      (node (ref "C33") (pin "1") (pinfunction "P$1_1") (pintype "passive"))
      (node (ref "C40") (pin "1") (pinfunction "P$1_1") (pintype "passive"))
      (node (ref "C41") (pin "1") (pinfunction "P$1_1") (pintype "passive"))
      (node (ref "C42") (pin "1") (pinfunction "P$1_1") (pintype "passive"))
      (node (ref "C43") (pin "1") (pinfunction "P$1_1") (pintype "passive"))
      (node (ref "C44") (pin "1") (pinfunction "P$1_1") (pintype "passive"))
      (node (ref "C45") (pin "1") (pinfunction "P$1_1") (pintype "passive"))
      (node (ref "C46") (pin "1") (pinfunction "P$1_1") (pintype "passive"))
      (node (ref "C47") (pin "1") (pinfunction "P$1_1") (pintype "passive"))
      (node (ref "C48") (pin "1") (pinfunction "P$1_1") (pintype "passive"))
      (node (ref "C49") (pin "1") (pinfunction "P$1_1") (pintype "passive"))
      (node (ref "C7") (pin "2") (pinfunction "P$2_2") (pintype "passive"))
      (node (ref "C8") (pin "2") (pinfunction "P$2_2") (pintype "passive"))
      (node (ref "D1") (pin "1") (pinfunction "A1_1") (pintype "passive"))
      (node (ref "D10") (pin "1") (pinfunction "A1_1") (pintype "passive"))
      (node (ref "D11") (pin "1") (pinfunction "A1_1") (pintype "passive"))
      (node (ref "D12") (pin "1") (pinfunction "A1_1") (pintype "passive"))
      (node (ref "D13") (pin "1") (pinfunction "A1_1") (pintype "passive"))
      (node (ref "D14") (pin "1") (pinfunction "A1_1") (pintype "passive"))
      (node (ref "D15") (pin "1") (pinfunction "A1_1") (pintype "passive"))
      (node (ref "D16") (pin "1") (pinfunction "A1_1") (pintype "passive"))
      (node (ref "D17") (pin "1") (pinfunction "A1_1") (pintype "passive"))
      (node (ref "D18") (pin "1") (pinfunction "A1_1") (pintype "passive"))
      (node (ref "D2") (pin "1") (pinfunction "A1_1") (pintype "passive"))
      (node (ref "D3") (pin "1") (pinfunction "A1_1") (pintype "passive"))
      (node (ref "D4") (pin "1") (pinfunction "A1_1") (pintype "passive"))
      (node (ref "D5") (pin "3") (pinfunction "3_3") (pintype "passive"))
      (node (ref "D6") (pin "1") (pinfunction "A1_1") (pintype "passive"))
      (node (ref "D7") (pin "1") (pinfunction "A1_1") (pintype "passive"))
      (node (ref "D8") (pin "1") (pinfunction "A1_1") (pintype "passive"))
      (node (ref "D9") (pin "1") (pinfunction "A1_1") (pintype "passive"))
      (node (ref "DA1") (pin "2") (pinfunction "GND_2") (pintype "power_in"))
      (node (ref "GND31") (pin "1") (pinfunction "1_1") (pintype "passive"))
      (node (ref "GND35") (pin "1") (pinfunction "1_1") (pintype "passive"))
      (node (ref "GND8") (pin "2") (pinfunction "2_2") (pintype "passive"))
      (node (ref "GND84") (pin "1") (pinfunction "1_1") (pintype "passive"))
      (node (ref "GND91") (pin "1") (pinfunction "1_1") (pintype "passive"))
      (node (ref "GND92") (pin "1") (pinfunction "1_1") (pintype "passive"))
      (node (ref "IC3") (pin "1") (pinfunction "A0_1") (pintype "input"))
      (node (ref "IC3") (pin "2") (pinfunction "A1_2") (pintype "input"))
      (node (ref "IC3") (pin "3") (pinfunction "A2_3") (pintype "input"))
      (node (ref "IC3") (pin "4") (pinfunction "GND_4") (pintype "power_in"))
      (node (ref "IC3") (pin "7") (pinfunction "WP_7") (pintype "input"))
      (node (ref "J7") (pin "3") (pinfunction "3_3") (pintype "passive"))
      (node (ref "R10") (pin "1") (pinfunction "1_1") (pintype "passive"))
      (node (ref "R12") (pin "1") (pinfunction "1_1") (pintype "passive"))
      (node (ref "R15") (pin "1") (pinfunction "1_1") (pintype "passive"))
      (node (ref "R18") (pin "1") (pinfunction "1_1") (pintype "passive"))
      (node (ref "R21") (pin "1") (pinfunction "1_1") (pintype "passive"))
      (node (ref "R24") (pin "2") (pinfunction "2_2") (pintype "passive"))
      (node (ref "R26") (pin "1") (pinfunction "1_1") (pintype "passive"))
      (node (ref "R30") (pin "1") (pinfunction "1_1") (pintype "passive"))
      (node (ref "R33") (pin "1") (pinfunction "1_1") (pintype "passive"))
      (node (ref "R36") (pin "2") (pinfunction "2_2") (pintype "passive"))
      (node (ref "R38") (pin "1") (pinfunction "1_1") (pintype "passive"))
      (node (ref "R4") (pin "1") (pinfunction "1_1") (pintype "passive"))
      (node (ref "R41") (pin "1") (pinfunction "1_1") (pintype "passive"))
      (node (ref "R44") (pin "1") (pinfunction "1_1") (pintype "passive"))
      (node (ref "R47") (pin "1") (pinfunction "1_1") (pintype "passive"))
      (node (ref "R5") (pin "1") (pinfunction "1_1") (pintype "passive"))
      (node (ref "R50") (pin "1") (pinfunction "1_1") (pintype "passive"))
      (node (ref "R53") (pin "1") (pinfunction "1_1") (pintype "passive"))
      (node (ref "R56") (pin "1") (pinfunction "1_1") (pintype "passive"))
      (node (ref "R59") (pin "2") (pinfunction "2_2") (pintype "passive"))
      (node (ref "R63") (pin "2") (pinfunction "2_2") (pintype "passive"))
      (node (ref "R65") (pin "2") (pinfunction "2_2") (pintype "passive"))
      (node (ref "R9") (pin "1") (pinfunction "1_1") (pintype "passive"))
      (node (ref "S1") (pin "1") (pinfunction "1_1") (pintype "passive"))
      (node (ref "S1") (pin "2") (pinfunction "2_2") (pintype "passive"))
      (node (ref "S2") (pin "1") (pinfunction "1_1") (pintype "passive"))
      (node (ref "S2") (pin "2") (pinfunction "2_2") (pintype "passive"))
      (node (ref "TP2") (pin "TP") (pinfunction "PP_TP") (pintype "input"))
      (node (ref "U$4") (pin "GND") (pinfunction "GND_GND") (pintype "bidirectional"))
      (node (ref "U1") (pin "12") (pinfunction "VSSA_12") (pintype "power_in"))
      (node (ref "U1") (pin "18") (pinfunction "VSS_4_18") (pintype "power_in"))
      (node (ref "U1") (pin "31") (pinfunction "VSS_1_31") (pintype "power_in"))
      (node (ref "U1") (pin "47") (pinfunction "VSS_2_47") (pintype "power_in"))
      (node (ref "U1") (pin "63") (pinfunction "VSS_3_63") (pintype "power_in"))
      (node (ref "X1") (pin "3") (pinfunction "3_3") (pintype "passive"))
      (node (ref "X1") (pin "7") (pinfunction "7_7") (pintype "passive"))
      (node (ref "X1") (pin "8") (pinfunction "8_8") (pintype "passive"))
      (node (ref "X1") (pin "S1") (pinfunction "S_S1") (pintype "passive"))
      (node (ref "X1") (pin "S2") (pinfunction "S_S2") (pintype "passive"))
      (node (ref "X2") (pin "3") (pinfunction "3_3") (pintype "passive"))
      (node (ref "X2") (pin "7") (pinfunction "7_7") (pintype "passive"))
      (node (ref "X2") (pin "8") (pinfunction "8_8") (pintype "passive"))
      (node (ref "X2") (pin "S1") (pinfunction "S_S1") (pintype "passive"))
      (node (ref "X2") (pin "S2") (pinfunction "S_S2") (pintype "passive"))
    )
    (net (code "27") (name "HARDWARE_RESET") (class "Default")
      (node (ref "R35") (pin "2") (pinfunction "2_2") (pintype "passive"))
      (node (ref "S2") (pin "3") (pinfunction "3_3") (pintype "passive"))
      (node (ref "S2") (pin "4") (pinfunction "4_4") (pintype "passive"))
      (node (ref "U1") (pin "61") (pinfunction "PB8_61") (pintype "bidirectional"))
    )
    (net (code "28") (name "I2C1_SCL") (class "Default")
      (node (ref "IC3") (pin "6") (pinfunction "SCL_6") (pintype "bidirectional"))
      (node (ref "R3") (pin "1") (pinfunction "1_1") (pintype "passive"))
      (node (ref "U1") (pin "58") (pinfunction "PB6_58") (pintype "bidirectional"))
    )
    (net (code "29") (name "I2C1_SDA") (class "Default")
      (node (ref "IC3") (pin "5") (pinfunction "SDA_5") (pintype "bidirectional"))
      (node (ref "R27") (pin "1") (pinfunction "1_1") (pintype "passive"))
      (node (ref "U1") (pin "59") (pinfunction "PB7_59") (pintype "bidirectional"))
    )
    (net (code "30") (name "INPUT_1") (class "Default")
      (node (ref "ALARMS3") (pin "1") (pinfunction "1_1") (pintype "passive"))
      (node (ref "R8") (pin "1") (pinfunction "1_1") (pintype "passive"))
    )
    (net (code "31") (name "INPUT_2") (class "Default")
      (node (ref "ALARMS3") (pin "2") (pinfunction "2_2") (pintype "passive"))
      (node (ref "R7") (pin "1") (pinfunction "1_1") (pintype "passive"))
    )
    (net (code "32") (name "INPUT_3") (class "Default")
      (node (ref "ALARMS3") (pin "3") (pinfunction "3_3") (pintype "passive"))
      (node (ref "R14") (pin "1") (pinfunction "1_1") (pintype "passive"))
    )
    (net (code "33") (name "INPUT_4") (class "Default")
      (node (ref "ALARMS7") (pin "1") (pinfunction "1_1") (pintype "passive"))
      (node (ref "R17") (pin "1") (pinfunction "1_1") (pintype "passive"))
    )
    (net (code "34") (name "INPUT_5") (class "Default")
      (node (ref "ALARMS7") (pin "2") (pinfunction "2_2") (pintype "passive"))
      (node (ref "R20") (pin "1") (pinfunction "1_1") (pintype "passive"))
    )
    (net (code "35") (name "INPUT_6") (class "Default")
      (node (ref "ALARMS7") (pin "3") (pinfunction "3_3") (pintype "passive"))
      (node (ref "R23") (pin "1") (pinfunction "1_1") (pintype "passive"))
    )
    (net (code "36") (name "INPUT_7") (class "Default")
      (node (ref "ALARMS5") (pin "1") (pinfunction "1_1") (pintype "passive"))
      (node (ref "R29") (pin "1") (pinfunction "1_1") (pintype "passive"))
    )
    (net (code "37") (name "INPUT_8") (class "Default")
      (node (ref "ALARMS5") (pin "2") (pinfunction "2_2") (pintype "passive"))
      (node (ref "R32") (pin "1") (pinfunction "1_1") (pintype "passive"))
    )
    (net (code "38") (name "INPUT_9") (class "Default")
      (node (ref "ALARMS5") (pin "3") (pinfunction "3_3") (pintype "passive"))
      (node (ref "R37") (pin "1") (pinfunction "1_1") (pintype "passive"))
    )
    (net (code "39") (name "INPUT_10") (class "Default")
      (node (ref "ALARMS4") (pin "1") (pinfunction "1_1") (pintype "passive"))
      (node (ref "R40") (pin "1") (pinfunction "1_1") (pintype "passive"))
    )
    (net (code "40") (name "INPUT_11") (class "Default")
      (node (ref "ALARMS4") (pin "2") (pinfunction "2_2") (pintype "passive"))
      (node (ref "R43") (pin "1") (pinfunction "1_1") (pintype "passive"))
    )
    (net (code "41") (name "INPUT_12") (class "Default")
      (node (ref "ALARMS4") (pin "3") (pinfunction "3_3") (pintype "passive"))
      (node (ref "R46") (pin "1") (pinfunction "1_1") (pintype "passive"))
    )
    (net (code "42") (name "INPUT_13") (class "Default")
      (node (ref "ALARMS6") (pin "1") (pinfunction "1_1") (pintype "passive"))
      (node (ref "R49") (pin "1") (pinfunction "1_1") (pintype "passive"))
    )
    (net (code "43") (name "INPUT_14") (class "Default")
      (node (ref "ALARMS6") (pin "2") (pinfunction "2_2") (pintype "passive"))
      (node (ref "R52") (pin "1") (pinfunction "1_1") (pintype "passive"))
    )
    (net (code "44") (name "INPUT_15") (class "Default")
      (node (ref "ALARMS6") (pin "3") (pinfunction "3_3") (pintype "passive"))
      (node (ref "R55") (pin "1") (pinfunction "1_1") (pintype "passive"))
    )
    (net (code "45") (name "Net-(12V2-Pad2)") (class "Default")
      (node (ref "12V2") (pin "2") (pinfunction "2_2") (pintype "passive"))
      (node (ref "R60") (pin "1") (pinfunction "1_1") (pintype "passive"))
    )
    (net (code "46") (name "Net-(C11-P$2)") (class "Default")
      (node (ref "12V2") (pin "1") (pinfunction "1_1") (pintype "passive"))
      (node (ref "C11") (pin "2") (pinfunction "P$2_2") (pintype "passive"))
      (node (ref "R59") (pin "1") (pinfunction "1_1") (pintype "passive"))
      (node (ref "R62") (pin "1") (pinfunction "1_1") (pintype "passive"))
    )
    (net (code "47") (name "Net-(C30-P$2)") (class "Default")
      (node (ref "8MHZ1") (pin "2") (pinfunction "2_2") (pintype "passive"))
      (node (ref "C30") (pin "2") (pinfunction "P$2_2") (pintype "passive"))
      (node (ref "U1") (pin "6") (pinfunction "PD1/OSC=>_6") (pintype "bidirectional"))
    )
    (net (code "48") (name "Net-(C31-P$2)") (class "Default")
      (node (ref "8MHZ1") (pin "1") (pinfunction "1_1") (pintype "passive"))
      (node (ref "C31") (pin "2") (pinfunction "P$2_2") (pintype "passive"))
      (node (ref "U1") (pin "5") (pinfunction "PD0/OSC<=_5") (pintype "bidirectional"))
    )
    (net (code "49") (name "Net-(D1-C1A2)") (class "Default")
      (node (ref "D1") (pin "3") (pinfunction "C1A2_3") (pintype "passive"))
      (node (ref "R10") (pin "2") (pinfunction "2_2") (pintype "passive"))
      (node (ref "R11") (pin "1") (pinfunction "1_1") (pintype "passive"))
      (node (ref "R8") (pin "2") (pinfunction "2_2") (pintype "passive"))
    )
    (net (code "50") (name "Net-(D2-C1A2)") (class "Default")
      (node (ref "D2") (pin "3") (pinfunction "C1A2_3") (pintype "passive"))
      (node (ref "R12") (pin "2") (pinfunction "2_2") (pintype "passive"))
      (node (ref "R13") (pin "1") (pinfunction "1_1") (pintype "passive"))
      (node (ref "R7") (pin "2") (pinfunction "2_2") (pintype "passive"))
    )
    (net (code "51") (name "Net-(D3-C1A2)") (class "Default")
      (node (ref "D3") (pin "3") (pinfunction "C1A2_3") (pintype "passive"))
      (node (ref "R14") (pin "2") (pinfunction "2_2") (pintype "passive"))
      (node (ref "R15") (pin "2") (pinfunction "2_2") (pintype "passive"))
      (node (ref "R16") (pin "1") (pinfunction "1_1") (pintype "passive"))
    )
    (net (code "52") (name "Net-(D4-C1A2)") (class "Default")
      (node (ref "D4") (pin "3") (pinfunction "C1A2_3") (pintype "passive"))
      (node (ref "R17") (pin "2") (pinfunction "2_2") (pintype "passive"))
      (node (ref "R18") (pin "2") (pinfunction "2_2") (pintype "passive"))
      (node (ref "R19") (pin "1") (pinfunction "1_1") (pintype "passive"))
    )
    (net (code "53") (name "Net-(D6-C1A2)") (class "Default")
      (node (ref "D6") (pin "3") (pinfunction "C1A2_3") (pintype "passive"))
      (node (ref "R58") (pin "1") (pinfunction "1_1") (pintype "passive"))
      (node (ref "R6") (pin "2") (pinfunction "2_2") (pintype "passive"))
      (node (ref "R9") (pin "2") (pinfunction "2_2") (pintype "passive"))
    )
    (net (code "54") (name "Net-(D7-C1A2)") (class "Default")
      (node (ref "D7") (pin "3") (pinfunction "C1A2_3") (pintype "passive"))
      (node (ref "R20") (pin "2") (pinfunction "2_2") (pintype "passive"))
      (node (ref "R21") (pin "2") (pinfunction "2_2") (pintype "passive"))
      (node (ref "R22") (pin "1") (pinfunction "1_1") (pintype "passive"))
    )
    (net (code "55") (name "Net-(D8-C1A2)") (class "Default")
      (node (ref "D8") (pin "3") (pinfunction "C1A2_3") (pintype "passive"))
      (node (ref "R23") (pin "2") (pinfunction "2_2") (pintype "passive"))
      (node (ref "R26") (pin "2") (pinfunction "2_2") (pintype "passive"))
      (node (ref "R28") (pin "1") (pinfunction "1_1") (pintype "passive"))
    )
    (net (code "56") (name "Net-(D9-C1A2)") (class "Default")
      (node (ref "D9") (pin "3") (pinfunction "C1A2_3") (pintype "passive"))
      (node (ref "R29") (pin "2") (pinfunction "2_2") (pintype "passive"))
      (node (ref "R30") (pin "2") (pinfunction "2_2") (pintype "passive"))
      (node (ref "R31") (pin "1") (pinfunction "1_1") (pintype "passive"))
    )
    (net (code "57") (name "Net-(D10-C1A2)") (class "Default")
      (node (ref "D10") (pin "3") (pinfunction "C1A2_3") (pintype "passive"))
      (node (ref "R32") (pin "2") (pinfunction "2_2") (pintype "passive"))
      (node (ref "R33") (pin "2") (pinfunction "2_2") (pintype "passive"))
      (node (ref "R34") (pin "1") (pinfunction "1_1") (pintype "passive"))
    )
    (net (code "58") (name "Net-(D11-C1A2)") (class "Default")
      (node (ref "D11") (pin "3") (pinfunction "C1A2_3") (pintype "passive"))
      (node (ref "R37") (pin "2") (pinfunction "2_2") (pintype "passive"))
      (node (ref "R38") (pin "2") (pinfunction "2_2") (pintype "passive"))
      (node (ref "R39") (pin "1") (pinfunction "1_1") (pintype "passive"))
    )
    (net (code "59") (name "Net-(D12-C1A2)") (class "Default")
      (node (ref "D12") (pin "3") (pinfunction "C1A2_3") (pintype "passive"))
      (node (ref "R40") (pin "2") (pinfunction "2_2") (pintype "passive"))
      (node (ref "R41") (pin "2") (pinfunction "2_2") (pintype "passive"))
      (node (ref "R42") (pin "1") (pinfunction "1_1") (pintype "passive"))
    )
    (net (code "60") (name "Net-(D13-C1A2)") (class "Default")
      (node (ref "D13") (pin "3") (pinfunction "C1A2_3") (pintype "passive"))
      (node (ref "R43") (pin "2") (pinfunction "2_2") (pintype "passive"))
      (node (ref "R44") (pin "2") (pinfunction "2_2") (pintype "passive"))
      (node (ref "R45") (pin "1") (pinfunction "1_1") (pintype "passive"))
    )
    (net (code "61") (name "Net-(D14-C1A2)") (class "Default")
      (node (ref "D14") (pin "3") (pinfunction "C1A2_3") (pintype "passive"))
      (node (ref "R46") (pin "2") (pinfunction "2_2") (pintype "passive"))
      (node (ref "R47") (pin "2") (pinfunction "2_2") (pintype "passive"))
      (node (ref "R48") (pin "1") (pinfunction "1_1") (pintype "passive"))
    )
    (net (code "62") (name "Net-(D15-C1A2)") (class "Default")
      (node (ref "D15") (pin "3") (pinfunction "C1A2_3") (pintype "passive"))
      (node (ref "R49") (pin "2") (pinfunction "2_2") (pintype "passive"))
      (node (ref "R50") (pin "2") (pinfunction "2_2") (pintype "passive"))
      (node (ref "R51") (pin "1") (pinfunction "1_1") (pintype "passive"))
    )
    (net (code "63") (name "Net-(D16-C1A2)") (class "Default")
      (node (ref "D16") (pin "3") (pinfunction "C1A2_3") (pintype "passive"))
      (node (ref "R52") (pin "2") (pinfunction "2_2") (pintype "passive"))
      (node (ref "R53") (pin "2") (pinfunction "2_2") (pintype "passive"))
      (node (ref "R54") (pin "1") (pinfunction "1_1") (pintype "passive"))
    )
    (net (code "64") (name "Net-(D17-C1A2)") (class "Default")
      (node (ref "D17") (pin "3") (pinfunction "C1A2_3") (pintype "passive"))
      (node (ref "R55") (pin "2") (pinfunction "2_2") (pintype "passive"))
      (node (ref "R56") (pin "2") (pinfunction "2_2") (pintype "passive"))
      (node (ref "R57") (pin "1") (pinfunction "1_1") (pintype "passive"))
    )
    (net (code "65") (name "Net-(D18-C1A2)") (class "Default")
      (node (ref "D18") (pin "3") (pinfunction "C1A2_3") (pintype "passive"))
      (node (ref "R61") (pin "1") (pinfunction "1_1") (pintype "passive"))
      (node (ref "R62") (pin "2") (pinfunction "2_2") (pintype "passive"))
    )
    (net (code "66") (name "Net-(DA1-RS)") (class "Default")
      (node (ref "DA1") (pin "8") (pinfunction "RS_8") (pintype "bidirectional"))
      (node (ref "R24") (pin "1") (pinfunction "1_1") (pintype "passive"))
    )
    (net (code "67") (name "Net-(F1-Pad2)") (class "Default")
      (node (ref "F1") (pin "2") (pinfunction "2_2") (pintype "passive"))
      (node (ref "U$4") (pin "OUT") (pinfunction "OUT_OUT") (pintype "bidirectional"))
    )
    (net (code "68") (name "Net-(JP2-Pad2)") (class "Default")
      (node (ref "JP2") (pin "2") (pinfunction "2_2") (pintype "passive"))
      (node (ref "R2") (pin "1") (pinfunction "1_1") (pintype "passive"))
    )
    (net (code "69") (name "Net-(LED1-PadC)") (class "Default")
      (node (ref "LED1") (pin "C") (pinfunction "C_C") (pintype "passive"))
      (node (ref "R5") (pin "2") (pinfunction "2_2") (pintype "passive"))
    )
    (net (code "70") (name "Net-(LED2-PadC)") (class "Default")
      (node (ref "LED2") (pin "C") (pinfunction "C_C") (pintype "passive"))
      (node (ref "R4") (pin "2") (pinfunction "2_2") (pintype "passive"))
    )
    (net (code "71") (name "Net-(R63-Pad1)") (class "Default")
      (node (ref "R63") (pin "1") (pinfunction "1_1") (pintype "passive"))
      (node (ref "SJ1") (pin "3") (pinfunction "3_3") (pintype "passive"))
    )
    (net (code "72") (name "Net-(R64-Pad1)") (class "Default")
      (node (ref "R64") (pin "1") (pinfunction "1_1") (pintype "passive"))
      (node (ref "SJ1") (pin "1") (pinfunction "1_1") (pintype "passive"))
    )
    (net (code "73") (name "Net-(R65-Pad1)") (class "Default")
      (node (ref "R65") (pin "1") (pinfunction "1_1") (pintype "passive"))
      (node (ref "SJ2") (pin "3") (pinfunction "3_3") (pintype "passive"))
    )
    (net (code "74") (name "Net-(R66-Pad1)") (class "Default")
      (node (ref "R66") (pin "1") (pinfunction "1_1") (pintype "passive"))
      (node (ref "SJ2") (pin "1") (pinfunction "1_1") (pintype "passive"))
    )
    (net (code "75") (name "PRE_FUSE_12V") (class "Default")
      (node (ref "F2") (pin "1") (pinfunction "1_1") (pintype "passive"))
      (node (ref "GND8") (pin "1") (pinfunction "1_1") (pintype "passive"))
      (node (ref "X1") (pin "4") (pinfunction "4_4") (pintype "passive"))
      (node (ref "X1") (pin "5") (pinfunction "5_5") (pintype "passive"))
      (node (ref "X1") (pin "6") (pinfunction "6_6") (pintype "passive"))
      (node (ref "X2") (pin "4") (pinfunction "4_4") (pintype "passive"))
      (node (ref "X2") (pin "5") (pinfunction "5_5") (pintype "passive"))
      (node (ref "X2") (pin "6") (pinfunction "6_6") (pintype "passive"))
    )
    (net (code "76") (name "RESET") (class "Default")
      (node (ref "R1") (pin "2") (pinfunction "2_2") (pintype "passive"))
      (node (ref "S1") (pin "3") (pinfunction "3_3") (pintype "passive"))
      (node (ref "S1") (pin "4") (pinfunction "4_4") (pintype "passive"))
      (node (ref "U1") (pin "7") (pinfunction "NRST_7") (pintype "input"))
    )
    (net (code "77") (name "SWCLK") (class "Default")
      (node (ref "J7") (pin "2") (pinfunction "2_2") (pintype "passive"))
      (node (ref "U1") (pin "49") (pinfunction "PA14_49") (pintype "bidirectional"))
    )
    (net (code "78") (name "SWDIO") (class "Default")
      (node (ref "J7") (pin "4") (pinfunction "4_4") (pintype "passive"))
      (node (ref "U1") (pin "46") (pinfunction "PA13_46") (pintype "bidirectional"))
    )
    (net (code "79") (name "TAMPER") (class "Default")
      (node (ref "R61") (pin "2") (pinfunction "2_2") (pintype "passive"))
      (node (ref "U1") (pin "33") (pinfunction "PB12_33") (pintype "bidirectional"))
    )
    (net (code "80") (name "UART_RX") (class "Default")
      (node (ref "J1") (pin "1") (pinfunction "1_1") (pintype "passive"))
      (node (ref "U1") (pin "43") (pinfunction "PA10_43") (pintype "bidirectional"))
    )
    (net (code "81") (name "UART_TX") (class "Default")
      (node (ref "J1") (pin "2") (pinfunction "2_2") (pintype "passive"))
      (node (ref "U1") (pin "42") (pinfunction "PA9_42") (pintype "bidirectional"))
    )
    (net (code "82") (name "unconnected-(DA1-VREF-Pad5)") (class "Default")
      (node (ref "DA1") (pin "5") (pinfunction "VREF_5") (pintype "bidirectional"))
    )
    (net (code "83") (name "unconnected-(U$4-PadEN)") (class "Default")
      (node (ref "U$4") (pin "EN") (pinfunction "EN_EN") (pintype "bidirectional"))
    )
    (net (code "84") (name "unconnected-(U1B-PA8-Pad41)") (class "Default")
      (node (ref "U1") (pin "41") (pinfunction "PA8_41") (pintype "bidirectional"))
    )
    (net (code "85") (name "unconnected-(U1B-PA15-Pad50)") (class "Default")
      (node (ref "U1") (pin "50") (pinfunction "PA15_50") (pintype "bidirectional"))
    )
    (net (code "86") (name "unconnected-(U1D-PB9-Pad62)") (class "Default")
      (node (ref "U1") (pin "62") (pinfunction "PB9_62") (pintype "bidirectional"))
    )
    (net (code "87") (name "unconnected-(U1D-PB10-Pad29)") (class "Default")
      (node (ref "U1") (pin "29") (pinfunction "PB10_29") (pintype "bidirectional"))
    )
    (net (code "88") (name "unconnected-(U1D-PB11-Pad30)") (class "Default")
      (node (ref "U1") (pin "30") (pinfunction "PB11_30") (pintype "bidirectional"))
    )
    (net (code "89") (name "unconnected-(U1D-PB13-Pad34)") (class "Default")
      (node (ref "U1") (pin "34") (pinfunction "PB13_34") (pintype "bidirectional"))
    )
    (net (code "90") (name "unconnected-(U1D-PB14-Pad35)") (class "Default")
      (node (ref "U1") (pin "35") (pinfunction "PB14_35") (pintype "bidirectional"))
    )
    (net (code "91") (name "unconnected-(U1D-PB15-Pad36)") (class "Default")
      (node (ref "U1") (pin "36") (pinfunction "PB15_36") (pintype "bidirectional"))
    )
    (net (code "92") (name "unconnected-(U1E-PB3-Pad55)") (class "Default")
      (node (ref "U1") (pin "55") (pinfunction "PB3_55") (pintype "bidirectional"))
    )
    (net (code "93") (name "unconnected-(U1E-PB4-Pad56)") (class "Default")
      (node (ref "U1") (pin "56") (pinfunction "PB4_56") (pintype "bidirectional"))
    )
    (net (code "94") (name "unconnected-(U1E-PB5-Pad57)") (class "Default")
      (node (ref "U1") (pin "57") (pinfunction "PB5_57") (pintype "bidirectional"))
    )
    (net (code "95") (name "unconnected-(U1F-PC8-Pad39)") (class "Default")
      (node (ref "U1") (pin "39") (pinfunction "PC8_39") (pintype "bidirectional"))
    )
    (net (code "96") (name "unconnected-(U1F-PC9-Pad40)") (class "Default")
      (node (ref "U1") (pin "40") (pinfunction "PC9_40") (pintype "bidirectional"))
    )
    (net (code "97") (name "unconnected-(U1F-PC10-Pad51)") (class "Default")
      (node (ref "U1") (pin "51") (pinfunction "PC10_51") (pintype "bidirectional"))
    )
    (net (code "98") (name "unconnected-(U1F-PC11-Pad52)") (class "Default")
      (node (ref "U1") (pin "52") (pinfunction "PC11_52") (pintype "bidirectional"))
    )
    (net (code "99") (name "unconnected-(U1F-PC12-Pad53)") (class "Default")
      (node (ref "U1") (pin "53") (pinfunction "PC12_53") (pintype "bidirectional"))
    )
    (net (code "100") (name "unconnected-(U1F-PC14-Pad3)") (class "Default")
      (node (ref "U1") (pin "3") (pinfunction "PC14_3") (pintype "bidirectional"))
    )
    (net (code "101") (name "unconnected-(U1F-PC15-Pad4)") (class "Default")
      (node (ref "U1") (pin "4") (pinfunction "PC15_4") (pintype "bidirectional"))
    )
    (net (code "102") (name "unconnected-(U1G-PC6-Pad37)") (class "Default")
      (node (ref "U1") (pin "37") (pinfunction "PC6_37") (pintype "bidirectional"))
    )
    (net (code "103") (name "unconnected-(U1G-PC7-Pad38)") (class "Default")
      (node (ref "U1") (pin "38") (pinfunction "PC7_38") (pintype "bidirectional"))
    )
    (net (code "104") (name "unconnected-(U1H-PD2-Pad54)") (class "Default")
      (node (ref "U1") (pin "54") (pinfunction "PD2_54") (pintype "bidirectional"))
    )
  )
)
